# DLP.net
KiCad netlist of a schematic drawn in Altium Designer
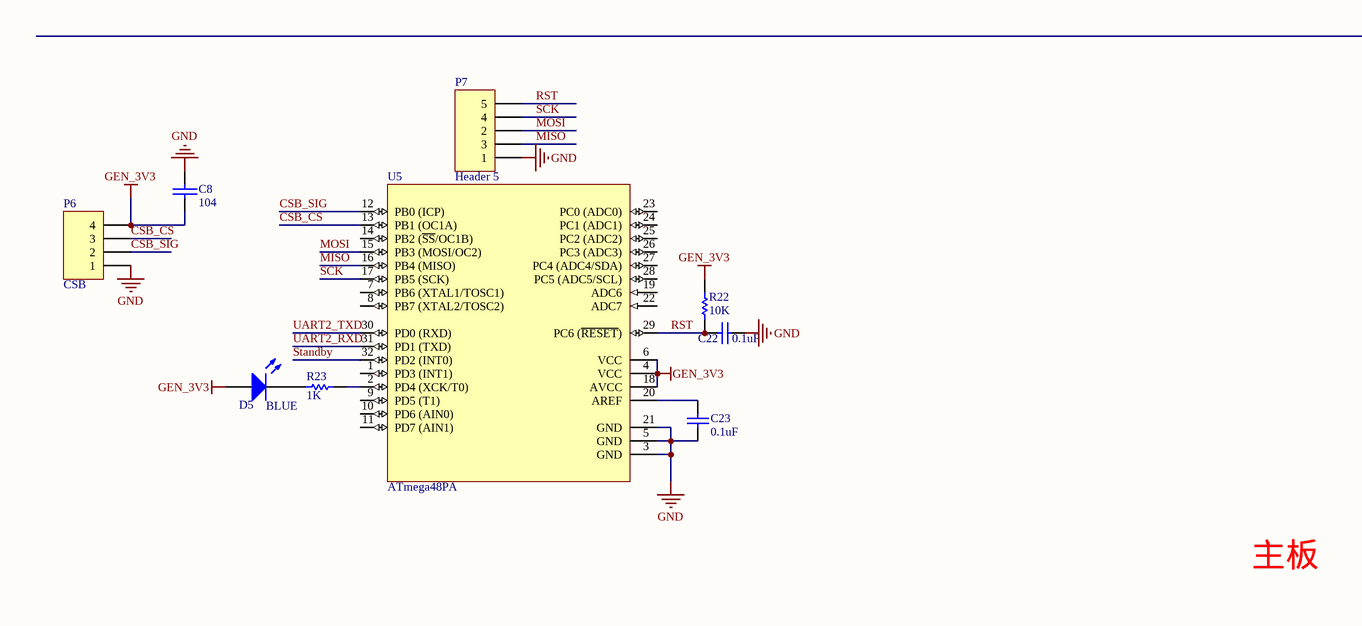
[diagram p0: DLP.SchDoc, top left]
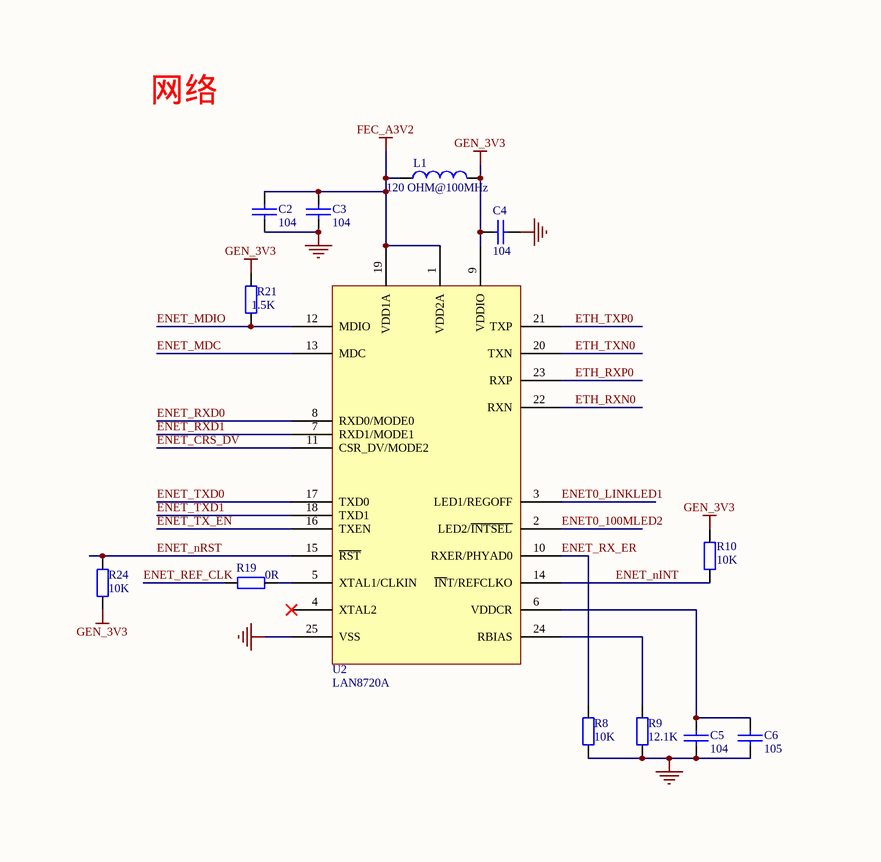
[diagram p1: DLP.SchDoc, top right]
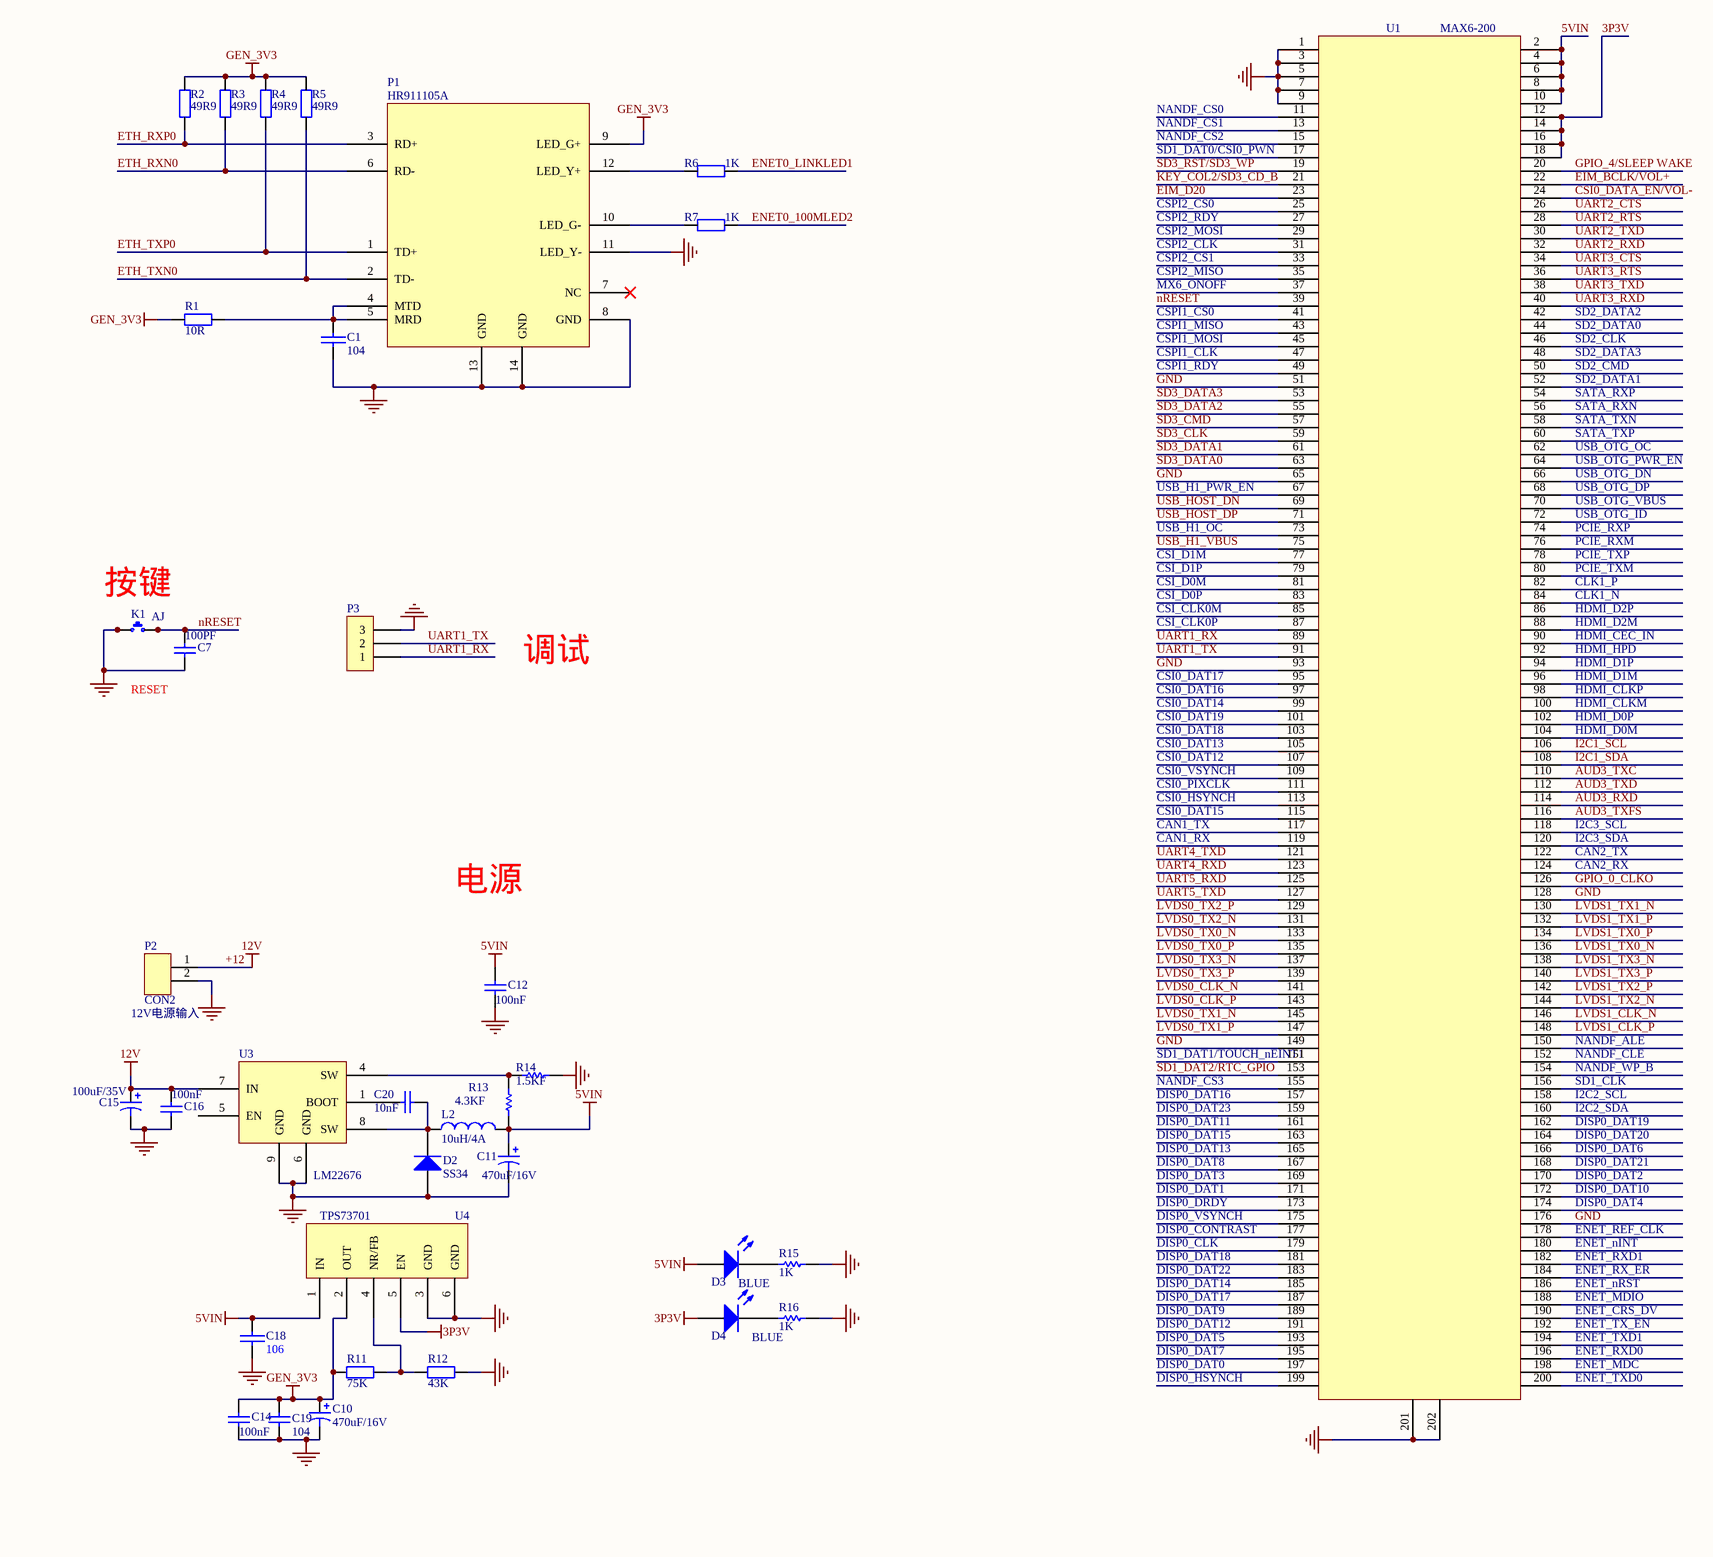
[diagram p2: DLP.SchDoc, bottom left]
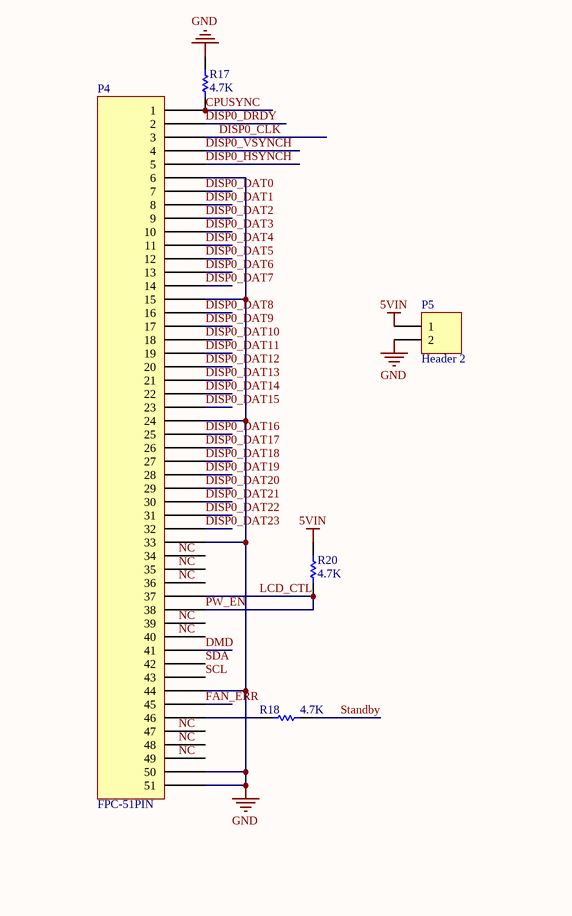
[diagram p3: DLP.SchDoc, bottom right]

(export (version "E")
  (design (tool "Eeschema 10.0.6"))
  (components
    (comp (ref "C1") (value "104") (footprint "0603") (libsource (lib "*") (part "CAP")))
    (comp (ref "C2") (value "104") (footprint "0603") (libsource (lib "*") (part "CAP")))
    (comp (ref "C3") (value "104") (footprint "0603") (libsource (lib "*") (part "CAP")))
    (comp (ref "C4") (value "104") (footprint "0603") (libsource (lib "*") (part "CAP")))
    (comp (ref "C5") (value "104") (footprint "0603") (libsource (lib "*") (part "CAP")))
    (comp (ref "C6") (value "105") (footprint "0603") (libsource (lib "*") (part "CAP")))
    (comp (ref "C7")
      (value "100PF")
      (footprint "0603")
      (description "Capacitor")
      (libsource (lib "*") (part "Cap"))
    )
    (comp (ref "C8") (value "104") (footprint "0603") (libsource (lib "*") (part "CAP")))
    (comp (ref "C10")
      (value "470uF/16V")
      (footprint "3216[1206]")
      (description "Polarized Capacitor (Radial)")
      (libsource (lib "*") (part "Cap Pol1"))
    )
    (comp (ref "C11")
      (value "470uF/16V")
      (footprint "C6.3*12")
      (description "Polarized Capacitor (Radial)")
      (libsource (lib "*") (part "Cap Pol1"))
    )
    (comp (ref "C12")
      (value "100nF")
      (footprint "0603")
      (description "Capacitor")
      (libsource (lib "*") (part "Cap"))
    )
    (comp (ref "C14")
      (value "100nF")
      (footprint "0603")
      (description "Capacitor")
      (libsource (lib "*") (part "Cap"))
    )
    (comp (ref "C15")
      (value "100uF/35V")
      (footprint "C6.3*12")
      (description "Polarized Capacitor (Radial)")
      (libsource (lib "*") (part "Cap Pol1"))
    )
    (comp (ref "C16")
      (value "100nF")
      (footprint "0603")
      (description "Capacitor")
      (libsource (lib "*") (part "Cap"))
    )
    (comp (ref "C18") (value "106") (footprint "0603") (libsource (lib "") (part "CAP_1")))
    (comp (ref "C19")
      (value "104")
      (footprint "0603")
      (fields (field (name "PUBLISHER") "Altium Limited"))
      (libsource (lib "*") (part "Cap"))
    )
    (comp (ref "C20")
      (value "10nF")
      (footprint "0603")
      (description "Capacitor")
      (libsource (lib "*") (part "Cap"))
    )
    (comp (ref "C22")
      (value "0.1uF")
      (footprint "0603")
      (description "Capacitor")
      (fields (field (name "Comment") "Cap") (field (name "PUBLISHER") "Altium Limited"))
      (libsource (lib "Miscellaneous Devices") (part "Cap"))
    )
    (comp (ref "C23")
      (value "0.1uF")
      (footprint "0603")
      (description "Capacitor")
      (fields (field (name "Comment") "Cap") (field (name "PUBLISHER") "Altium Limited"))
      (libsource (lib "Miscellaneous Devices") (part "Cap"))
    )
    (comp (ref "D2")
      (value "SS34")
      (footprint "SMA")
      (description "3 Amp Medium Power Silicon Rectifier Diode")
      (libsource (lib "*") (part "Diode 1N5408"))
    )
    (comp (ref "D3")
      (value "BLUE")
      (footprint "0603-LED")
      (description "Typical RED, GREEN, YELLOW, AMBER GaAs LED")
      (libsource (lib "*") (part "LED2"))
    )
    (comp (ref "D4")
      (value "BLUE")
      (footprint "0603-LED")
      (description "Typical RED, GREEN, YELLOW, AMBER GaAs LED")
      (libsource (lib "*") (part "LED2"))
    )
    (comp (ref "D5")
      (value "BLUE")
      (footprint "0603-LED")
      (description "Typical RED, GREEN, YELLOW, AMBER GaAs LED")
      (libsource (lib "*") (part "LED2"))
    )
    (comp (ref "K1") (value "AJ") (footprint "4*4*1.5") (libsource (lib "*") (part "KEY_1")))
    (comp (ref "L1")
      (value "120 OHM@100MHz")
      (footprint "0603")
      (description "Inductor")
      (libsource (lib "*") (part "Inductor"))
    )
    (comp (ref "L2")
      (value "10uH/4A")
      (footprint "8040")
      (description "Inductor")
      (libsource (lib "*") (part "Inductor"))
    )
    (comp (ref "P1") (value "HR911105A") (footprint "HR911105A") (libsource (lib "*") (part "HR911105A")))
    (comp (ref "P2") (value "CON2") (footprint "PH2.0-2P") (libsource (lib "*") (part "CON2")))
    (comp (ref "P3")
      (value "~")
      (footprint "HDR1X3")
      (description "Connector")
      (libsource (lib "*") (part "CON3"))
    )
    (comp (ref "P4")
      (value "FPC-51PIN")
      (footprint "FH26-51S-0.3SHW")
      (libsource (lib "TANK") (part "FPC-51PIN"))
    )
    (comp (ref "P5")
      (value "Header 2")
      (footprint "PH2.0-2P")
      (description "Header, 2-Pin")
      (fields (field (name "PUBLISHER") "Altium Limited"))
      (libsource (lib "Miscellaneous Connectors") (part "Header 2"))
    )
    (comp (ref "P6")
      (value "CSB")
      (footprint "HDR1X4")
      (description "Header, 4-Pin")
      (fields (field (name "PUBLISHER") "Altium Limited"))
      (libsource (lib "Miscellaneous Connectors") (part "Header 4"))
    )
    (comp (ref "P7")
      (value "Header 5")
      (footprint "HDR1X5")
      (description "Header, 5-Pin")
      (fields (field (name "PUBLISHER") "Altium Limited"))
      (libsource (lib "Miscellaneous Connectors") (part "Header 5"))
    )
    (comp (ref "R1") (value "10R") (footprint "0603") (libsource (lib "*") (part "RES")))
    (comp (ref "R2") (value "49R9") (footprint "0603") (libsource (lib "*") (part "RES")))
    (comp (ref "R3") (value "49R9") (footprint "0603") (libsource (lib "*") (part "RES")))
    (comp (ref "R4") (value "49R9") (footprint "0603") (libsource (lib "*") (part "RES")))
    (comp (ref "R5") (value "49R9") (footprint "0603") (libsource (lib "*") (part "RES")))
    (comp (ref "R6") (value "1K") (footprint "0603") (libsource (lib "*") (part "RES")))
    (comp (ref "R7") (value "1K") (footprint "0603") (libsource (lib "*") (part "RES")))
    (comp (ref "R8") (value "10K") (footprint "0603") (libsource (lib "*") (part "RES")))
    (comp (ref "R9") (value "12.1K") (footprint "0603") (libsource (lib "*") (part "RES")))
    (comp (ref "R10") (value "10K") (footprint "0603") (libsource (lib "*") (part "RES")))
    (comp (ref "R11")
      (value "75K")
      (footprint "0603")
      (description "Resistor")
      (fields (field (name "PUBLISHER") "Altium Limited"))
      (libsource (lib "*") (part "Res2"))
    )
    (comp (ref "R12")
      (value "43K")
      (footprint "0603")
      (description "Resistor")
      (fields (field (name "PUBLISHER") "Altium Limited"))
      (libsource (lib "") (part "Res2_1"))
    )
    (comp (ref "R13")
      (value "4.3KF")
      (footprint "0603")
      (description "Resistor")
      (libsource (lib "*") (part "Res1"))
    )
    (comp (ref "R14")
      (value "1.5KF")
      (footprint "0603")
      (description "Resistor")
      (libsource (lib "*") (part "Res1"))
    )
    (comp (ref "R15")
      (value "1K")
      (footprint "0603")
      (description "Resistor")
      (libsource (lib "*") (part "Res1"))
    )
    (comp (ref "R16")
      (value "1K")
      (footprint "0603")
      (description "Resistor")
      (libsource (lib "*") (part "Res1"))
    )
    (comp (ref "R17")
      (value "4.7K")
      (footprint "0603")
      (description "Resistor")
      (fields (field (name "Comment") "Res1") (field (name "PUBLISHER") "Altium Limited"))
      (libsource (lib "Miscellaneous Devices") (part "Res1"))
    )
    (comp (ref "R18")
      (value "4.7K")
      (footprint "0603")
      (description "Resistor")
      (fields (field (name "Comment") "Res1") (field (name "PUBLISHER") "Altium Limited"))
      (libsource (lib "Miscellaneous Devices") (part "Res1"))
    )
    (comp (ref "R19") (value "0R") (footprint "0603") (libsource (lib "*") (part "RES")))
    (comp (ref "R20")
      (value "4.7K")
      (footprint "0603")
      (description "Resistor")
      (fields (field (name "Comment") "Res1") (field (name "PUBLISHER") "Altium Limited"))
      (libsource (lib "Miscellaneous Devices") (part "Res1"))
    )
    (comp (ref "R21") (value "1.5K") (footprint "0603R") (libsource (lib "*") (part "RES")))
    (comp (ref "R22")
      (value "10K")
      (footprint "0603")
      (description "Resistor")
      (fields (field (name "Comment") "Res1") (field (name "PUBLISHER") "Altium Limited"))
      (libsource (lib "Miscellaneous Devices") (part "Res1"))
    )
    (comp (ref "R23")
      (value "1K")
      (footprint "0603")
      (description "Resistor")
      (libsource (lib "*") (part "Res1"))
    )
    (comp (ref "R24") (value "10K") (footprint "0603") (libsource (lib "*") (part "RES")))
    (comp (ref "U1") (value "MAX6-200") (footprint "SO-DIMM 200") (libsource (lib "*") (part "MAX6-200")))
    (comp (ref "U2") (value "LAN8720A") (footprint "QFN24_4X4MM") (libsource (lib "*") (part "LAN8720A")))
    (comp (ref "U3") (value "LM22676") (footprint "SO-8HP") (libsource (lib "*") (part "LM22676")))
    (comp (ref "U4") (value "TPS73701") (footprint "SOT223-6") (libsource (lib "*") (part "TPS737")))
    (comp (ref "U5")
      (value "ATmega48PA")
      (footprint "32A_M")
      (description "8-Bit AVR Microcontroller with 8K Bytes of In-System Programmable Flash Memory")
      (fields (field (name "PUBLISHER") "Altium Limited"))
      (libsource (lib "Atmel Microcontroller 8-Bit AVR") (part "ATmega8-16AC"))
    )
  )
  (nets
    (net (code "1") (name "/AUD3_RXD") (class "Default") (node (ref "U1") (pin "114") (pintype "passive")))
    (net (code "2") (name "/AUD3_TXC") (class "Default") (node (ref "U1") (pin "110") (pintype "passive")))
    (net (code "3") (name "/AUD3_TXD") (class "Default") (node (ref "U1") (pin "112") (pintype "passive")))
    (net (code "4") (name "/AUD3_TXFS") (class "Default") (node (ref "U1") (pin "116") (pintype "passive")))
    (net (code "5") (name "/CAN1_RX") (class "Default") (node (ref "U1") (pin "119") (pintype "passive")))
    (net (code "6") (name "/CAN1_TX") (class "Default") (node (ref "U1") (pin "117") (pintype "passive")))
    (net (code "7") (name "/CAN2_RX") (class "Default") (node (ref "U1") (pin "124") (pintype "passive")))
    (net (code "8") (name "/CAN2_TX") (class "Default") (node (ref "U1") (pin "122") (pintype "passive")))
    (net (code "9") (name "/CLK1_N") (class "Default") (node (ref "U1") (pin "84") (pintype "passive")))
    (net (code "10") (name "/CLK1_P") (class "Default") (node (ref "U1") (pin "82") (pintype "passive")))
    (net (code "11") (name "/CPUSYNC") (class "Default")
      (node (ref "P4") (pin "1") (pinfunction "1_1") (pintype "passive"))
      (node (ref "R17") (pin "2") (pinfunction "2_2") (pintype "passive"))
    )
    (net (code "12") (name "/CSB_CS") (class "Default")
      (node (ref "P6") (pin "3") (pinfunction "3_3") (pintype "passive"))
      (node (ref "U5") (pin "13") (pinfunction "PB1_(OC1A)_13") (pintype "bidirectional"))
    )
    (net (code "13") (name "/CSB_SIG") (class "Default")
      (node (ref "P6") (pin "2") (pinfunction "2_2") (pintype "passive"))
      (node (ref "U5") (pin "12") (pinfunction "PB0_(ICP)_12") (pintype "bidirectional"))
    )
    (net (code "14") (name "/CSI0_DAT12") (class "Default") (node (ref "U1") (pin "107") (pintype "passive")))
    (net (code "15") (name "/CSI0_DAT13") (class "Default") (node (ref "U1") (pin "105") (pintype "passive")))
    (net (code "16") (name "/CSI0_DAT14") (class "Default") (node (ref "U1") (pin "99") (pintype "passive")))
    (net (code "17") (name "/CSI0_DAT15") (class "Default") (node (ref "U1") (pin "115") (pintype "passive")))
    (net (code "18") (name "/CSI0_DAT16") (class "Default") (node (ref "U1") (pin "97") (pintype "passive")))
    (net (code "19") (name "/CSI0_DAT17") (class "Default") (node (ref "U1") (pin "95") (pintype "passive")))
    (net (code "20") (name "/CSI0_DAT18") (class "Default") (node (ref "U1") (pin "103") (pintype "passive")))
    (net (code "21") (name "/CSI0_DAT19") (class "Default") (node (ref "U1") (pin "101") (pintype "passive")))
    (net (code "22") (name "/CSI0_DATA_EN{slash}VOL-") (class "Default")
      (node (ref "U1") (pin "24") (pintype "passive"))
    )
    (net (code "23") (name "/CSI0_HSYNCH") (class "Default")
      (node (ref "U1") (pin "113") (pintype "passive"))
    )
    (net (code "24") (name "/CSI0_PIXCLK") (class "Default")
      (node (ref "U1") (pin "111") (pintype "passive"))
    )
    (net (code "25") (name "/CSI0_VSYNCH") (class "Default")
      (node (ref "U1") (pin "109") (pintype "passive"))
    )
    (net (code "26") (name "/CSI_CLK0M") (class "Default") (node (ref "U1") (pin "85") (pintype "passive")))
    (net (code "27") (name "/CSI_CLK0P") (class "Default") (node (ref "U1") (pin "87") (pintype "passive")))
    (net (code "28") (name "/CSI_D0M") (class "Default") (node (ref "U1") (pin "81") (pintype "passive")))
    (net (code "29") (name "/CSI_D0P") (class "Default") (node (ref "U1") (pin "83") (pintype "passive")))
    (net (code "30") (name "/CSI_D1M") (class "Default") (node (ref "U1") (pin "77") (pintype "passive")))
    (net (code "31") (name "/CSI_D1P") (class "Default") (node (ref "U1") (pin "79") (pintype "passive")))
    (net (code "32") (name "/CSPI1_CLK") (class "Default") (node (ref "U1") (pin "47") (pintype "passive")))
    (net (code "33") (name "/CSPI1_CS0") (class "Default") (node (ref "U1") (pin "41") (pintype "passive")))
    (net (code "34") (name "/CSPI1_MISO") (class "Default") (node (ref "U1") (pin "43") (pintype "passive")))
    (net (code "35") (name "/CSPI1_MOSI") (class "Default") (node (ref "U1") (pin "45") (pintype "passive")))
    (net (code "36") (name "/CSPI1_RDY") (class "Default") (node (ref "U1") (pin "49") (pintype "passive")))
    (net (code "37") (name "/CSPI2_CLK") (class "Default") (node (ref "U1") (pin "31") (pintype "passive")))
    (net (code "38") (name "/CSPI2_CS0") (class "Default") (node (ref "U1") (pin "25") (pintype "passive")))
    (net (code "39") (name "/CSPI2_CS1") (class "Default") (node (ref "U1") (pin "33") (pintype "passive")))
    (net (code "40") (name "/CSPI2_MISO") (class "Default") (node (ref "U1") (pin "35") (pintype "passive")))
    (net (code "41") (name "/CSPI2_MOSI") (class "Default") (node (ref "U1") (pin "29") (pintype "passive")))
    (net (code "42") (name "/CSPI2_RDY") (class "Default") (node (ref "U1") (pin "27") (pintype "passive")))
    (net (code "43") (name "/DISP0_CLK") (class "Default")
      (node (ref "P4") (pin "3") (pinfunction "3_3") (pintype "passive"))
      (node (ref "U1") (pin "179") (pintype "passive"))
    )
    (net (code "44") (name "/DISP0_CONTRAST") (class "Default")
      (node (ref "U1") (pin "177") (pintype "passive"))
    )
    (net (code "45") (name "/DISP0_DAT0") (class "Default")
      (node (ref "P4") (pin "7") (pinfunction "7_7") (pintype "passive"))
      (node (ref "U1") (pin "197") (pintype "passive"))
    )
    (net (code "46") (name "/DISP0_DAT1") (class "Default")
      (node (ref "P4") (pin "8") (pinfunction "8_8") (pintype "passive"))
      (node (ref "U1") (pin "171") (pintype "passive"))
    )
    (net (code "47") (name "/DISP0_DAT2") (class "Default")
      (node (ref "P4") (pin "9") (pinfunction "9_9") (pintype "passive"))
      (node (ref "U1") (pin "170") (pintype "passive"))
    )
    (net (code "48") (name "/DISP0_DAT3") (class "Default")
      (node (ref "P4") (pin "10") (pinfunction "10_10") (pintype "passive"))
      (node (ref "U1") (pin "169") (pintype "passive"))
    )
    (net (code "49") (name "/DISP0_DAT4") (class "Default")
      (node (ref "P4") (pin "11") (pinfunction "11_11") (pintype "passive"))
      (node (ref "U1") (pin "174") (pintype "passive"))
    )
    (net (code "50") (name "/DISP0_DAT5") (class "Default")
      (node (ref "P4") (pin "12") (pinfunction "12_12") (pintype "passive"))
      (node (ref "U1") (pin "193") (pintype "passive"))
    )
    (net (code "51") (name "/DISP0_DAT6") (class "Default")
      (node (ref "P4") (pin "13") (pinfunction "13_13") (pintype "passive"))
      (node (ref "U1") (pin "166") (pintype "passive"))
    )
    (net (code "52") (name "/DISP0_DAT7") (class "Default")
      (node (ref "P4") (pin "14") (pinfunction "14_14") (pintype "passive"))
      (node (ref "U1") (pin "195") (pintype "passive"))
    )
    (net (code "53") (name "/DISP0_DAT8") (class "Default")
      (node (ref "P4") (pin "16") (pinfunction "16_16") (pintype "passive"))
      (node (ref "U1") (pin "167") (pintype "passive"))
    )
    (net (code "54") (name "/DISP0_DAT9") (class "Default")
      (node (ref "P4") (pin "17") (pinfunction "17_17") (pintype "passive"))
      (node (ref "U1") (pin "189") (pintype "passive"))
    )
    (net (code "55") (name "/DISP0_DAT10") (class "Default")
      (node (ref "P4") (pin "18") (pinfunction "18_18") (pintype "passive"))
      (node (ref "U1") (pin "172") (pintype "passive"))
    )
    (net (code "56") (name "/DISP0_DAT11") (class "Default")
      (node (ref "P4") (pin "19") (pinfunction "19_19") (pintype "passive"))
      (node (ref "U1") (pin "161") (pintype "passive"))
    )
    (net (code "57") (name "/DISP0_DAT12") (class "Default")
      (node (ref "P4") (pin "20") (pinfunction "20_20") (pintype "passive"))
      (node (ref "U1") (pin "191") (pintype "passive"))
    )
    (net (code "58") (name "/DISP0_DAT13") (class "Default")
      (node (ref "P4") (pin "21") (pinfunction "21_21") (pintype "passive"))
      (node (ref "U1") (pin "165") (pintype "passive"))
    )
    (net (code "59") (name "/DISP0_DAT14") (class "Default")
      (node (ref "P4") (pin "22") (pinfunction "22_22") (pintype "passive"))
      (node (ref "U1") (pin "185") (pintype "passive"))
    )
    (net (code "60") (name "/DISP0_DAT15") (class "Default")
      (node (ref "P4") (pin "23") (pinfunction "23_23") (pintype "passive"))
      (node (ref "U1") (pin "163") (pintype "passive"))
    )
    (net (code "61") (name "/DISP0_DAT16") (class "Default")
      (node (ref "P4") (pin "25") (pinfunction "25_25") (pintype "passive"))
      (node (ref "U1") (pin "157") (pintype "passive"))
    )
    (net (code "62") (name "/DISP0_DAT17") (class "Default")
      (node (ref "P4") (pin "26") (pinfunction "26_26") (pintype "passive"))
      (node (ref "U1") (pin "187") (pintype "passive"))
    )
    (net (code "63") (name "/DISP0_DAT18") (class "Default")
      (node (ref "P4") (pin "27") (pinfunction "27_27") (pintype "passive"))
      (node (ref "U1") (pin "181") (pintype "passive"))
    )
    (net (code "64") (name "/DISP0_DAT19") (class "Default")
      (node (ref "P4") (pin "28") (pinfunction "28_28") (pintype "passive"))
      (node (ref "U1") (pin "162") (pintype "passive"))
    )
    (net (code "65") (name "/DISP0_DAT20") (class "Default")
      (node (ref "P4") (pin "29") (pinfunction "29_29") (pintype "passive"))
      (node (ref "U1") (pin "164") (pintype "passive"))
    )
    (net (code "66") (name "/DISP0_DAT21") (class "Default")
      (node (ref "P4") (pin "30") (pinfunction "30_30") (pintype "passive"))
      (node (ref "U1") (pin "168") (pintype "passive"))
    )
    (net (code "67") (name "/DISP0_DAT22") (class "Default")
      (node (ref "P4") (pin "31") (pinfunction "31_31") (pintype "passive"))
      (node (ref "U1") (pin "183") (pintype "passive"))
    )
    (net (code "68") (name "/DISP0_DAT23") (class "Default")
      (node (ref "P4") (pin "32") (pinfunction "32_32") (pintype "passive"))
      (node (ref "U1") (pin "159") (pintype "passive"))
    )
    (net (code "69") (name "/DISP0_DRDY") (class "Default")
      (node (ref "P4") (pin "2") (pinfunction "2_2") (pintype "passive"))
      (node (ref "U1") (pin "173") (pintype "passive"))
    )
    (net (code "70") (name "/DISP0_HSYNCH") (class "Default")
      (node (ref "P4") (pin "5") (pinfunction "5_5") (pintype "passive"))
      (node (ref "U1") (pin "199") (pintype "passive"))
    )
    (net (code "71") (name "/DISP0_VSYNCH") (class "Default")
      (node (ref "P4") (pin "4") (pinfunction "4_4") (pintype "passive"))
      (node (ref "U1") (pin "175") (pintype "passive"))
    )
    (net (code "72") (name "/DMD") (class "Default")
      (node (ref "P4") (pin "41") (pinfunction "41_41") (pintype "passive"))
    )
    (net (code "73") (name "/EIM_BCLK{slash}VOL+") (class "Default")
      (node (ref "U1") (pin "22") (pintype "passive"))
    )
    (net (code "74") (name "/EIM_D20") (class "Default") (node (ref "U1") (pin "23") (pintype "passive")))
    (net (code "75") (name "/ENET0_100MLED2") (class "Default")
      (node (ref "R7") (pin "2") (pinfunction "2_2") (pintype "passive"))
      (node (ref "U2") (pin "2") (pinfunction "LED2/~{INTSEL}_2") (pintype "passive"))
    )
    (net (code "76") (name "/ENET0_LINKLED1") (class "Default")
      (node (ref "R6") (pin "2") (pinfunction "2_2") (pintype "passive"))
      (node (ref "U2") (pin "3") (pinfunction "LED1/REGOFF_3") (pintype "passive"))
    )
    (net (code "77") (name "/ENET_CRS_DV") (class "Default")
      (node (ref "U1") (pin "190") (pintype "passive"))
      (node (ref "U2") (pin "11") (pinfunction "CSR_DV/MODE2_11") (pintype "passive"))
    )
    (net (code "78") (name "/ENET_MDC") (class "Default")
      (node (ref "U1") (pin "198") (pintype "passive"))
      (node (ref "U2") (pin "13") (pinfunction "MDC_13") (pintype "passive"))
    )
    (net (code "79") (name "/ENET_MDIO") (class "Default")
      (node (ref "R21") (pin "1") (pinfunction "1_1") (pintype "passive"))
      (node (ref "U1") (pin "188") (pintype "passive"))
      (node (ref "U2") (pin "12") (pinfunction "MDIO_12") (pintype "passive"))
    )
    (net (code "80") (name "/ENET_REF_CLK") (class "Default")
      (node (ref "R19") (pin "2") (pinfunction "2_2") (pintype "passive"))
      (node (ref "U1") (pin "178") (pintype "passive"))
    )
    (net (code "81") (name "/ENET_RXD0") (class "Default")
      (node (ref "U1") (pin "196") (pintype "passive"))
      (node (ref "U2") (pin "8") (pinfunction "RXD0/MODE0_8") (pintype "passive"))
    )
    (net (code "82") (name "/ENET_RXD1") (class "Default")
      (node (ref "U1") (pin "182") (pintype "passive"))
      (node (ref "U2") (pin "7") (pinfunction "RXD1/MODE1_7") (pintype "passive"))
    )
    (net (code "83") (name "/ENET_RX_ER") (class "Default")
      (node (ref "R8") (pin "2") (pinfunction "2_2") (pintype "passive"))
      (node (ref "U1") (pin "184") (pintype "passive"))
      (node (ref "U2") (pin "10") (pinfunction "RXER/PHYAD0_10") (pintype "passive"))
    )
    (net (code "84") (name "/ENET_TXD0") (class "Default")
      (node (ref "U1") (pin "200") (pintype "passive"))
      (node (ref "U2") (pin "17") (pinfunction "TXD0_17") (pintype "passive"))
    )
    (net (code "85") (name "/ENET_TXD1") (class "Default")
      (node (ref "U1") (pin "194") (pintype "passive"))
      (node (ref "U2") (pin "18") (pinfunction "TXD1_18") (pintype "passive"))
    )
    (net (code "86") (name "/ENET_TX_EN") (class "Default")
      (node (ref "U1") (pin "192") (pintype "passive"))
      (node (ref "U2") (pin "16") (pinfunction "TXEN_16") (pintype "passive"))
    )
    (net (code "87") (name "/ENET_nINT") (class "Default")
      (node (ref "R10") (pin "1") (pinfunction "1_1") (pintype "passive"))
      (node (ref "U1") (pin "180") (pintype "passive"))
      (node (ref "U2") (pin "14") (pinfunction "~{IN}T/REFCLKO_14") (pintype "passive"))
    )
    (net (code "88") (name "/ENET_nRST") (class "Default")
      (node (ref "R24") (pin "2") (pinfunction "2_2") (pintype "passive"))
      (node (ref "U1") (pin "186") (pintype "passive"))
      (node (ref "U2") (pin "15") (pinfunction "~{RST}_15") (pintype "passive"))
    )
    (net (code "89") (name "/ETH_RXN0") (class "Default")
      (node (ref "P1") (pin "6") (pinfunction "RD-_6") (pintype "passive"))
      (node (ref "R3") (pin "1") (pinfunction "1_1") (pintype "passive"))
      (node (ref "U2") (pin "22") (pinfunction "RXN_22") (pintype "passive"))
    )
    (net (code "90") (name "/ETH_RXP0") (class "Default")
      (node (ref "P1") (pin "3") (pinfunction "RD+_3") (pintype "passive"))
      (node (ref "R2") (pin "1") (pinfunction "1_1") (pintype "passive"))
      (node (ref "U2") (pin "23") (pinfunction "RXP_23") (pintype "passive"))
    )
    (net (code "91") (name "/ETH_TXN0") (class "Default")
      (node (ref "P1") (pin "2") (pinfunction "TD-_2") (pintype "passive"))
      (node (ref "R5") (pin "1") (pinfunction "1_1") (pintype "passive"))
      (node (ref "U2") (pin "20") (pinfunction "TXN_20") (pintype "passive"))
    )
    (net (code "92") (name "/ETH_TXP0") (class "Default")
      (node (ref "P1") (pin "1") (pinfunction "TD+_1") (pintype "passive"))
      (node (ref "R4") (pin "1") (pinfunction "1_1") (pintype "passive"))
      (node (ref "U2") (pin "21") (pinfunction "TXP_21") (pintype "passive"))
    )
    (net (code "93") (name "/FAN_ERR") (class "Default")
      (node (ref "P4") (pin "45") (pinfunction "45_45") (pintype "passive"))
    )
    (net (code "94") (name "/GPIO_0_CLKO") (class "Default")
      (node (ref "U1") (pin "126") (pintype "passive"))
    )
    (net (code "95") (name "/GPIO_4{slash}SLEEP WAKE") (class "Default")
      (node (ref "U1") (pin "20") (pintype "passive"))
    )
    (net (code "96") (name "/HDMI_CEC_IN") (class "Default") (node (ref "U1") (pin "90") (pintype "passive")))
    (net (code "97") (name "/HDMI_CLKM") (class "Default") (node (ref "U1") (pin "100") (pintype "passive")))
    (net (code "98") (name "/HDMI_CLKP") (class "Default") (node (ref "U1") (pin "98") (pintype "passive")))
    (net (code "99") (name "/HDMI_D0M") (class "Default") (node (ref "U1") (pin "104") (pintype "passive")))
    (net (code "100") (name "/HDMI_D0P") (class "Default") (node (ref "U1") (pin "102") (pintype "passive")))
    (net (code "101") (name "/HDMI_D1M") (class "Default") (node (ref "U1") (pin "96") (pintype "passive")))
    (net (code "102") (name "/HDMI_D1P") (class "Default") (node (ref "U1") (pin "94") (pintype "passive")))
    (net (code "103") (name "/HDMI_D2M") (class "Default") (node (ref "U1") (pin "88") (pintype "passive")))
    (net (code "104") (name "/HDMI_D2P") (class "Default") (node (ref "U1") (pin "86") (pintype "passive")))
    (net (code "105") (name "/HDMI_HPD") (class "Default") (node (ref "U1") (pin "92") (pintype "passive")))
    (net (code "106") (name "/I2C1_SCL") (class "Default") (node (ref "U1") (pin "106") (pintype "passive")))
    (net (code "107") (name "/I2C1_SDA") (class "Default") (node (ref "U1") (pin "108") (pintype "passive")))
    (net (code "108") (name "/I2C2_SCL") (class "Default") (node (ref "U1") (pin "158") (pintype "passive")))
    (net (code "109") (name "/I2C2_SDA") (class "Default") (node (ref "U1") (pin "160") (pintype "passive")))
    (net (code "110") (name "/I2C3_SCL") (class "Default") (node (ref "U1") (pin "118") (pintype "passive")))
    (net (code "111") (name "/I2C3_SDA") (class "Default") (node (ref "U1") (pin "120") (pintype "passive")))
    (net (code "112") (name "/KEY_COL2{slash}SD3_CD_B") (class "Default")
      (node (ref "U1") (pin "21") (pintype "passive"))
    )
    (net (code "113") (name "/LCD_CTL") (class "Default")
      (node (ref "P4") (pin "37") (pinfunction "37_37") (pintype "passive"))
      (node (ref "P4") (pin "38") (pinfunction "38_38") (pintype "passive"))
      (node (ref "R20") (pin "2") (pinfunction "2_2") (pintype "passive"))
    )
    (net (code "114") (name "/LVDS0_CLK_N") (class "Default")
      (node (ref "U1") (pin "141") (pintype "passive"))
    )
    (net (code "115") (name "/LVDS0_CLK_P") (class "Default")
      (node (ref "U1") (pin "143") (pintype "passive"))
    )
    (net (code "116") (name "/LVDS0_TX0_N") (class "Default")
      (node (ref "U1") (pin "133") (pintype "passive"))
    )
    (net (code "117") (name "/LVDS0_TX0_P") (class "Default")
      (node (ref "U1") (pin "135") (pintype "passive"))
    )
    (net (code "118") (name "/LVDS0_TX1_N") (class "Default")
      (node (ref "U1") (pin "145") (pintype "passive"))
    )
    (net (code "119") (name "/LVDS0_TX1_P") (class "Default")
      (node (ref "U1") (pin "147") (pintype "passive"))
    )
    (net (code "120") (name "/LVDS0_TX2_N") (class "Default")
      (node (ref "U1") (pin "131") (pintype "passive"))
    )
    (net (code "121") (name "/LVDS0_TX2_P") (class "Default")
      (node (ref "U1") (pin "129") (pintype "passive"))
    )
    (net (code "122") (name "/LVDS0_TX3_N") (class "Default")
      (node (ref "U1") (pin "137") (pintype "passive"))
    )
    (net (code "123") (name "/LVDS0_TX3_P") (class "Default")
      (node (ref "U1") (pin "139") (pintype "passive"))
    )
    (net (code "124") (name "/LVDS1_CLK_N") (class "Default")
      (node (ref "U1") (pin "146") (pintype "passive"))
    )
    (net (code "125") (name "/LVDS1_CLK_P") (class "Default")
      (node (ref "U1") (pin "148") (pintype "passive"))
    )
    (net (code "126") (name "/LVDS1_TX0_N") (class "Default")
      (node (ref "U1") (pin "136") (pintype "passive"))
    )
    (net (code "127") (name "/LVDS1_TX0_P") (class "Default")
      (node (ref "U1") (pin "134") (pintype "passive"))
    )
    (net (code "128") (name "/LVDS1_TX1_N") (class "Default")
      (node (ref "U1") (pin "130") (pintype "passive"))
    )
    (net (code "129") (name "/LVDS1_TX1_P") (class "Default")
      (node (ref "U1") (pin "132") (pintype "passive"))
    )
    (net (code "130") (name "/LVDS1_TX2_N") (class "Default")
      (node (ref "U1") (pin "144") (pintype "passive"))
    )
    (net (code "131") (name "/LVDS1_TX2_P") (class "Default")
      (node (ref "U1") (pin "142") (pintype "passive"))
    )
    (net (code "132") (name "/LVDS1_TX3_N") (class "Default")
      (node (ref "U1") (pin "138") (pintype "passive"))
    )
    (net (code "133") (name "/LVDS1_TX3_P") (class "Default")
      (node (ref "U1") (pin "140") (pintype "passive"))
    )
    (net (code "134") (name "/MISO") (class "Default")
      (node (ref "P7") (pin "3") (pinfunction "3_3") (pintype "passive"))
      (node (ref "U5") (pin "16") (pinfunction "PB4_(MISO)_16") (pintype "bidirectional"))
    )
    (net (code "135") (name "/MOSI") (class "Default")
      (node (ref "P7") (pin "2") (pinfunction "2_2") (pintype "passive"))
      (node (ref "U5") (pin "15") (pinfunction "PB3_(MOSI/OC2)_15") (pintype "bidirectional"))
    )
    (net (code "136") (name "/MX6_ONOFF") (class "Default") (node (ref "U1") (pin "37") (pintype "passive")))
    (net (code "137") (name "/NANDF_ALE") (class "Default") (node (ref "U1") (pin "150") (pintype "passive")))
    (net (code "138") (name "/NANDF_CLE") (class "Default") (node (ref "U1") (pin "152") (pintype "passive")))
    (net (code "139") (name "/NANDF_CS0") (class "Default") (node (ref "U1") (pin "11") (pintype "passive")))
    (net (code "140") (name "/NANDF_CS1") (class "Default") (node (ref "U1") (pin "13") (pintype "passive")))
    (net (code "141") (name "/NANDF_CS2") (class "Default") (node (ref "U1") (pin "15") (pintype "passive")))
    (net (code "142") (name "/NANDF_CS3") (class "Default") (node (ref "U1") (pin "155") (pintype "passive")))
    (net (code "143") (name "/NANDF_WP_B") (class "Default")
      (node (ref "U1") (pin "154") (pintype "passive"))
    )
    (net (code "145") (name "/PCIE_RXM") (class "Default") (node (ref "U1") (pin "76") (pintype "passive")))
    (net (code "146") (name "/PCIE_RXP") (class "Default") (node (ref "U1") (pin "74") (pintype "passive")))
    (net (code "147") (name "/PCIE_TXM") (class "Default") (node (ref "U1") (pin "80") (pintype "passive")))
    (net (code "148") (name "/PCIE_TXP") (class "Default") (node (ref "U1") (pin "78") (pintype "passive")))
    (net (code "149") (name "/RST") (class "Default")
      (node (ref "C22") (pin "1") (pinfunction "1_1") (pintype "passive"))
      (node (ref "P7") (pin "5") (pinfunction "5_5") (pintype "passive"))
      (node (ref "R22") (pin "1") (pinfunction "1_1") (pintype "passive"))
      (node (ref "U5") (pin "29") (pinfunction "PC6_(~{RESET})_29") (pintype "bidirectional"))
    )
    (net (code "150") (name "/SATA_RXN") (class "Default") (node (ref "U1") (pin "56") (pintype "passive")))
    (net (code "151") (name "/SATA_RXP") (class "Default") (node (ref "U1") (pin "54") (pintype "passive")))
    (net (code "152") (name "/SATA_TXN") (class "Default") (node (ref "U1") (pin "58") (pintype "passive")))
    (net (code "153") (name "/SATA_TXP") (class "Default") (node (ref "U1") (pin "60") (pintype "passive")))
    (net (code "154") (name "/SCK") (class "Default")
      (node (ref "P7") (pin "4") (pinfunction "4_4") (pintype "passive"))
      (node (ref "U5") (pin "17") (pinfunction "PB5_(SCK)_17") (pintype "bidirectional"))
    )
    (net (code "155") (name "/SCL") (class "Default")
      (node (ref "P4") (pin "43") (pinfunction "43_43") (pintype "passive"))
    )
    (net (code "156") (name "/SD1_CLK") (class "Default") (node (ref "U1") (pin "156") (pintype "passive")))
    (net (code "157") (name "/SD1_DAT0{slash}CSI0_PWN") (class "Default")
      (node (ref "U1") (pin "17") (pintype "passive"))
    )
    (net (code "158") (name "/SD1_DAT1{slash}TOUCH_nEINT1") (class "Default")
      (node (ref "U1") (pin "151") (pintype "passive"))
    )
    (net (code "159") (name "/SD1_DAT2{slash}RTC_GPIO") (class "Default")
      (node (ref "U1") (pin "153") (pintype "passive"))
    )
    (net (code "160") (name "/SD2_CLK") (class "Default") (node (ref "U1") (pin "46") (pintype "passive")))
    (net (code "161") (name "/SD2_CMD") (class "Default") (node (ref "U1") (pin "50") (pintype "passive")))
    (net (code "162") (name "/SD2_DATA0") (class "Default") (node (ref "U1") (pin "44") (pintype "passive")))
    (net (code "163") (name "/SD2_DATA1") (class "Default") (node (ref "U1") (pin "52") (pintype "passive")))
    (net (code "164") (name "/SD2_DATA2") (class "Default") (node (ref "U1") (pin "42") (pintype "passive")))
    (net (code "165") (name "/SD2_DATA3") (class "Default") (node (ref "U1") (pin "48") (pintype "passive")))
    (net (code "166") (name "/SD3_CLK") (class "Default") (node (ref "U1") (pin "59") (pintype "passive")))
    (net (code "167") (name "/SD3_CMD") (class "Default") (node (ref "U1") (pin "57") (pintype "passive")))
    (net (code "168") (name "/SD3_DATA0") (class "Default") (node (ref "U1") (pin "63") (pintype "passive")))
    (net (code "169") (name "/SD3_DATA1") (class "Default") (node (ref "U1") (pin "61") (pintype "passive")))
    (net (code "170") (name "/SD3_DATA2") (class "Default") (node (ref "U1") (pin "55") (pintype "passive")))
    (net (code "171") (name "/SD3_DATA3") (class "Default") (node (ref "U1") (pin "53") (pintype "passive")))
    (net (code "172") (name "/SD3_RST{slash}SD3_WP") (class "Default")
      (node (ref "U1") (pin "19") (pintype "passive"))
    )
    (net (code "173") (name "/SDA") (class "Default")
      (node (ref "P4") (pin "42") (pinfunction "42_42") (pintype "passive"))
    )
    (net (code "174") (name "/Standby") (class "Default")
      (node (ref "R18") (pin "2") (pinfunction "2_2") (pintype "passive"))
      (node (ref "U5") (pin "32") (pinfunction "PD2_(INT0)_32") (pintype "bidirectional"))
    )
    (net (code "175") (name "/UART1_RX") (class "Default")
      (node (ref "P3") (pin "1") (pinfunction "1_1") (pintype "passive"))
      (node (ref "U1") (pin "89") (pintype "passive"))
    )
    (net (code "176") (name "/UART1_TX") (class "Default")
      (node (ref "P3") (pin "2") (pinfunction "2_2") (pintype "passive"))
      (node (ref "U1") (pin "91") (pintype "passive"))
    )
    (net (code "177") (name "/UART2_CTS") (class "Default") (node (ref "U1") (pin "26") (pintype "passive")))
    (net (code "178") (name "/UART2_RTS") (class "Default") (node (ref "U1") (pin "28") (pintype "passive")))
    (net (code "179") (name "/UART2_RXD") (class "Default")
      (node (ref "U1") (pin "32") (pintype "passive"))
      (node (ref "U5") (pin "31") (pinfunction "PD1_(TXD)_31") (pintype "bidirectional"))
    )
    (net (code "180") (name "/UART2_TXD") (class "Default")
      (node (ref "U1") (pin "30") (pintype "passive"))
      (node (ref "U5") (pin "30") (pinfunction "PD0_(RXD)_30") (pintype "bidirectional"))
    )
    (net (code "181") (name "/UART3_CTS") (class "Default") (node (ref "U1") (pin "34") (pintype "passive")))
    (net (code "182") (name "/UART3_RTS") (class "Default") (node (ref "U1") (pin "36") (pintype "passive")))
    (net (code "183") (name "/UART3_RXD") (class "Default") (node (ref "U1") (pin "40") (pintype "passive")))
    (net (code "184") (name "/UART3_TXD") (class "Default") (node (ref "U1") (pin "38") (pintype "passive")))
    (net (code "185") (name "/UART4_RXD") (class "Default") (node (ref "U1") (pin "123") (pintype "passive")))
    (net (code "186") (name "/UART4_TXD") (class "Default") (node (ref "U1") (pin "121") (pintype "passive")))
    (net (code "187") (name "/UART5_RXD") (class "Default") (node (ref "U1") (pin "125") (pintype "passive")))
    (net (code "188") (name "/UART5_TXD") (class "Default") (node (ref "U1") (pin "127") (pintype "passive")))
    (net (code "189") (name "/USB_H1_OC") (class "Default") (node (ref "U1") (pin "73") (pintype "passive")))
    (net (code "190") (name "/USB_H1_PWR_EN") (class "Default")
      (node (ref "U1") (pin "67") (pintype "passive"))
    )
    (net (code "191") (name "/USB_H1_VBUS") (class "Default")
      (node (ref "U1") (pin "75") (pintype "passive"))
    )
    (net (code "192") (name "/USB_HOST_DN") (class "Default")
      (node (ref "U1") (pin "69") (pintype "passive"))
    )
    (net (code "193") (name "/USB_HOST_DP") (class "Default")
      (node (ref "U1") (pin "71") (pintype "passive"))
    )
    (net (code "194") (name "/USB_OTG_DN") (class "Default") (node (ref "U1") (pin "66") (pintype "passive")))
    (net (code "195") (name "/USB_OTG_DP") (class "Default") (node (ref "U1") (pin "68") (pintype "passive")))
    (net (code "196") (name "/USB_OTG_ID") (class "Default") (node (ref "U1") (pin "72") (pintype "passive")))
    (net (code "197") (name "/USB_OTG_OC") (class "Default") (node (ref "U1") (pin "62") (pintype "passive")))
    (net (code "198") (name "/USB_OTG_PWR_EN") (class "Default")
      (node (ref "U1") (pin "64") (pintype "passive"))
    )
    (net (code "199") (name "/USB_OTG_VBUS") (class "Default")
      (node (ref "U1") (pin "70") (pintype "passive"))
    )
    (net (code "200") (name "/nRESET") (class "Default")
      (node (ref "C7") (pin "2") (pinfunction "2_2") (pintype "passive"))
      (node (ref "K1") (pin "3") (pintype "passive"))
      (node (ref "K1") (pin "4") (pintype "passive"))
      (node (ref "U1") (pin "39") (pintype "passive"))
    )
    (net (code "201") (name "3P3V") (class "Default")
      (node (ref "D4") (pin "1") (pinfunction "A_1") (pintype "passive"))
      (node (ref "U1") (pin "12") (pintype "passive"))
      (node (ref "U1") (pin "14") (pintype "passive"))
      (node (ref "U1") (pin "16") (pintype "passive"))
      (node (ref "U1") (pin "18") (pintype "passive"))
      (node (ref "U4") (pin "5") (pinfunction "EN_5") (pintype "passive"))
    )
    (net (code "202") (name "5VIN") (class "Default")
      (node (ref "C11") (pin "1") (pinfunction "1_1") (pintype "passive"))
      (node (ref "C12") (pin "2") (pinfunction "2_2") (pintype "passive"))
      (node (ref "C18") (pin "1") (pintype "passive"))
      (node (ref "D3") (pin "1") (pinfunction "A_1") (pintype "passive"))
      (node (ref "L2") (pin "2") (pinfunction "2_2") (pintype "passive"))
      (node (ref "P5") (pin "1") (pinfunction "1_1") (pintype "passive"))
      (node (ref "R13") (pin "2") (pinfunction "2_2") (pintype "passive"))
      (node (ref "R20") (pin "1") (pinfunction "1_1") (pintype "passive"))
      (node (ref "U1") (pin "10") (pintype "passive"))
      (node (ref "U1") (pin "2") (pintype "passive"))
      (node (ref "U1") (pin "4") (pintype "passive"))
      (node (ref "U1") (pin "6") (pintype "passive"))
      (node (ref "U1") (pin "8") (pintype "passive"))
      (node (ref "U4") (pin "1") (pinfunction "IN_1") (pintype "passive"))
    )
    (net (code "203") (name "12V") (class "Default")
      (node (ref "C15") (pin "1") (pinfunction "1_1") (pintype "passive"))
      (node (ref "C16") (pin "2") (pinfunction "2_2") (pintype "passive"))
      (node (ref "P2") (pin "1") (pinfunction "1_1") (pintype "passive"))
      (node (ref "U3") (pin "7") (pinfunction "IN_7") (pintype "passive"))
    )
    (net (code "204") (name "FEC_A3V2") (class "Default")
      (node (ref "C2") (pin "1") (pintype "passive"))
      (node (ref "C3") (pin "1") (pintype "passive"))
      (node (ref "L1") (pin "1") (pinfunction "1_1") (pintype "passive"))
      (node (ref "U2") (pin "1") (pinfunction "VDD2A_1") (pintype "passive"))
      (node (ref "U2") (pin "19") (pinfunction "VDD1A_19") (pintype "passive"))
    )
    (net (code "205") (name "GEN_3V3") (class "Default")
      (node (ref "C10") (pin "1") (pinfunction "1_1") (pintype "passive"))
      (node (ref "C14") (pin "2") (pinfunction "2_2") (pintype "passive"))
      (node (ref "C19") (pin "2") (pinfunction "2_2") (pintype "passive"))
      (node (ref "C4") (pin "2") (pintype "passive"))
      (node (ref "C8") (pin "2") (pintype "passive"))
      (node (ref "D5") (pin "1") (pinfunction "A_1") (pintype "passive"))
      (node (ref "L1") (pin "2") (pinfunction "2_2") (pintype "passive"))
      (node (ref "P1") (pin "9") (pinfunction "LED_G+_9") (pintype "passive"))
      (node (ref "P6") (pin "4") (pinfunction "4_4") (pintype "passive"))
      (node (ref "R1") (pin "2") (pinfunction "2_2") (pintype "passive"))
      (node (ref "R10") (pin "2") (pinfunction "2_2") (pintype "passive"))
      (node (ref "R11") (pin "2") (pinfunction "2_2") (pintype "passive"))
      (node (ref "R2") (pin "2") (pinfunction "2_2") (pintype "passive"))
      (node (ref "R21") (pin "2") (pinfunction "2_2") (pintype "passive"))
      (node (ref "R22") (pin "2") (pinfunction "2_2") (pintype "passive"))
      (node (ref "R24") (pin "1") (pinfunction "1_1") (pintype "passive"))
      (node (ref "R3") (pin "2") (pinfunction "2_2") (pintype "passive"))
      (node (ref "R4") (pin "2") (pinfunction "2_2") (pintype "passive"))
      (node (ref "R5") (pin "2") (pinfunction "2_2") (pintype "passive"))
      (node (ref "U2") (pin "9") (pinfunction "VDDIO_9") (pintype "passive"))
      (node (ref "U4") (pin "2") (pinfunction "OUT_2") (pintype "passive"))
      (node (ref "U5") (pin "18") (pinfunction "AVCC_18") (pintype "power_in"))
      (node (ref "U5") (pin "4") (pinfunction "VCC_4") (pintype "power_in"))
      (node (ref "U5") (pin "6") (pinfunction "VCC_6") (pintype "power_in"))
    )
    (net (code "206") (name "GND") (class "Default")
      (node (ref "C1") (pin "2") (pintype "passive"))
      (node (ref "C10") (pin "2") (pinfunction "2_2") (pintype "passive"))
      (node (ref "C11") (pin "2") (pinfunction "2_2") (pintype "passive"))
      (node (ref "C12") (pin "1") (pinfunction "1_1") (pintype "passive"))
      (node (ref "C14") (pin "1") (pinfunction "1_1") (pintype "passive"))
      (node (ref "C15") (pin "2") (pinfunction "2_2") (pintype "passive"))
      (node (ref "C16") (pin "1") (pinfunction "1_1") (pintype "passive"))
      (node (ref "C18") (pin "2") (pintype "passive"))
      (node (ref "C19") (pin "1") (pinfunction "1_1") (pintype "passive"))
      (node (ref "C2") (pin "2") (pintype "passive"))
      (node (ref "C22") (pin "2") (pinfunction "2_2") (pintype "passive"))
      (node (ref "C23") (pin "2") (pinfunction "2_2") (pintype "passive"))
      (node (ref "C3") (pin "2") (pintype "passive"))
      (node (ref "C4") (pin "1") (pintype "passive"))
      (node (ref "C5") (pin "2") (pintype "passive"))
      (node (ref "C6") (pin "2") (pintype "passive"))
      (node (ref "C7") (pin "1") (pinfunction "1_1") (pintype "passive"))
      (node (ref "C8") (pin "1") (pintype "passive"))
      (node (ref "D2") (pin "1") (pinfunction "A_1") (pintype "passive"))
      (node (ref "K1") (pin "1") (pintype "passive"))
      (node (ref "K1") (pin "2") (pintype "passive"))
      (node (ref "P1") (pin "11") (pinfunction "LED_Y-_11") (pintype "passive"))
      (node (ref "P1") (pin "13") (pinfunction "GND_13") (pintype "passive"))
      (node (ref "P1") (pin "14") (pinfunction "GND_14") (pintype "passive"))
      (node (ref "P1") (pin "8") (pinfunction "GND_8") (pintype "passive"))
      (node (ref "P2") (pin "2") (pinfunction "2_2") (pintype "passive"))
      (node (ref "P3") (pin "3") (pinfunction "3_3") (pintype "passive"))
      (node (ref "P4") (pin "15") (pinfunction "15_15") (pintype "passive"))
      (node (ref "P4") (pin "24") (pinfunction "24_24") (pintype "passive"))
      (node (ref "P4") (pin "33") (pinfunction "33_33") (pintype "passive"))
      (node (ref "P4") (pin "44") (pinfunction "44_44") (pintype "passive"))
      (node (ref "P4") (pin "50") (pinfunction "50_50") (pintype "passive"))
      (node (ref "P4") (pin "51") (pinfunction "51_51") (pintype "passive"))
      (node (ref "P4") (pin "6") (pinfunction "6_6") (pintype "passive"))
      (node (ref "P5") (pin "2") (pinfunction "2_2") (pintype "passive"))
      (node (ref "P6") (pin "1") (pinfunction "1_1") (pintype "passive"))
      (node (ref "P7") (pin "1") (pinfunction "1_1") (pintype "passive"))
      (node (ref "R12") (pin "2") (pinfunction "2_2") (pintype "passive"))
      (node (ref "R14") (pin "2") (pinfunction "2_2") (pintype "passive"))
      (node (ref "R15") (pin "1") (pinfunction "1_1") (pintype "passive"))
      (node (ref "R16") (pin "1") (pinfunction "1_1") (pintype "passive"))
      (node (ref "R17") (pin "1") (pinfunction "1_1") (pintype "passive"))
      (node (ref "R8") (pin "1") (pinfunction "1_1") (pintype "passive"))
      (node (ref "R9") (pin "1") (pinfunction "1_1") (pintype "passive"))
      (node (ref "U1") (pin "1") (pintype "passive"))
      (node (ref "U1") (pin "128") (pintype "passive"))
      (node (ref "U1") (pin "149") (pintype "passive"))
      (node (ref "U1") (pin "176") (pintype "passive"))
      (node (ref "U1") (pin "201") (pintype "passive"))
      (node (ref "U1") (pin "202") (pintype "passive"))
      (node (ref "U1") (pin "3") (pintype "passive"))
      (node (ref "U1") (pin "5") (pintype "passive"))
      (node (ref "U1") (pin "51") (pintype "passive"))
      (node (ref "U1") (pin "65") (pintype "passive"))
      (node (ref "U1") (pin "7") (pintype "passive"))
      (node (ref "U1") (pin "9") (pintype "passive"))
      (node (ref "U1") (pin "93") (pintype "passive"))
      (node (ref "U2") (pin "25") (pinfunction "VSS_25") (pintype "passive"))
      (node (ref "U3") (pin "6") (pinfunction "GND_6") (pintype "passive"))
      (node (ref "U3") (pin "9") (pinfunction "GND_9") (pintype "passive"))
      (node (ref "U4") (pin "3") (pinfunction "GND_3") (pintype "passive"))
      (node (ref "U4") (pin "6") (pinfunction "GND_6") (pintype "passive"))
      (node (ref "U5") (pin "21") (pinfunction "GND_21") (pintype "power_in"))
      (node (ref "U5") (pin "3") (pinfunction "GND_3") (pintype "power_in"))
      (node (ref "U5") (pin "5") (pinfunction "GND_5") (pintype "power_in"))
    )
    (net (code "207") (name "Net-(D2-K)") (class "Default")
      (node (ref "C20") (pin "1") (pinfunction "1_1") (pintype "passive"))
      (node (ref "D2") (pin "2") (pinfunction "K_2") (pintype "passive"))
      (node (ref "L2") (pin "1") (pinfunction "1_1") (pintype "passive"))
      (node (ref "U3") (pin "8") (pinfunction "SW_8") (pintype "passive"))
    )
    (net (code "208") (name "Net-(D3-K)") (class "Default")
      (node (ref "D3") (pin "2") (pinfunction "K_2") (pintype "passive"))
      (node (ref "R15") (pin "2") (pinfunction "2_2") (pintype "passive"))
    )
    (net (code "209") (name "Net-(D4-K)") (class "Default")
      (node (ref "D4") (pin "2") (pinfunction "K_2") (pintype "passive"))
      (node (ref "R16") (pin "2") (pinfunction "2_2") (pintype "passive"))
    )
    (net (code "210") (name "Net-(D5-K)") (class "Default")
      (node (ref "D5") (pin "2") (pinfunction "K_2") (pintype "passive"))
      (node (ref "R23") (pin "2") (pinfunction "2_2") (pintype "passive"))
    )
    (net (code "211") (name "Net-(P1-LED_G-)") (class "Default")
      (node (ref "P1") (pin "10") (pinfunction "LED_G-_10") (pintype "passive"))
      (node (ref "R7") (pin "1") (pinfunction "1_1") (pintype "passive"))
    )
    (net (code "212") (name "Net-(P1-LED_Y+)") (class "Default")
      (node (ref "P1") (pin "12") (pinfunction "LED_Y+_12") (pintype "passive"))
      (node (ref "R6") (pin "1") (pinfunction "1_1") (pintype "passive"))
    )
    (net (code "213") (name "Net-(P1-MRD)") (class "Default")
      (node (ref "C1") (pin "1") (pintype "passive"))
      (node (ref "P1") (pin "4") (pinfunction "MTD_4") (pintype "passive"))
      (node (ref "P1") (pin "5") (pinfunction "MRD_5") (pintype "passive"))
      (node (ref "R1") (pin "1") (pinfunction "1_1") (pintype "passive"))
    )
    (net (code "214") (name "Net-(P4-Pad46)") (class "Default")
      (node (ref "P4") (pin "46") (pinfunction "46_46") (pintype "passive"))
      (node (ref "R18") (pin "1") (pinfunction "1_1") (pintype "passive"))
    )
    (net (code "215") (name "Net-(R13-Pad1)") (class "Default")
      (node (ref "R13") (pin "1") (pinfunction "1_1") (pintype "passive"))
      (node (ref "R14") (pin "1") (pinfunction "1_1") (pintype "passive"))
      (node (ref "U3") (pin "4") (pinfunction "SW_4") (pintype "passive"))
    )
    (net (code "216") (name "Net-(U2-RBIAS)") (class "Default")
      (node (ref "R9") (pin "2") (pinfunction "2_2") (pintype "passive"))
      (node (ref "U2") (pin "24") (pinfunction "RBIAS_24") (pintype "passive"))
    )
    (net (code "217") (name "Net-(U2-VDDCR)") (class "Default")
      (node (ref "C5") (pin "1") (pintype "passive"))
      (node (ref "C6") (pin "1") (pintype "passive"))
      (node (ref "U2") (pin "6") (pinfunction "VDDCR_6") (pintype "passive"))
    )
    (net (code "218") (name "Net-(U2-XTAL1{slash}CLKIN)") (class "Default")
      (node (ref "R19") (pin "1") (pinfunction "1_1") (pintype "passive"))
      (node (ref "U2") (pin "5") (pinfunction "XTAL1/CLKIN_5") (pintype "passive"))
    )
    (net (code "219") (name "Net-(U3-BOOT)") (class "Default")
      (node (ref "C20") (pin "2") (pinfunction "2_2") (pintype "passive"))
      (node (ref "U3") (pin "1") (pinfunction "BOOT_1") (pintype "passive"))
    )
    (net (code "220") (name "Net-(U4-NR{slash}FB)") (class "Default")
      (node (ref "R11") (pin "1") (pinfunction "1_1") (pintype "passive"))
      (node (ref "R12") (pin "1") (pinfunction "1_1") (pintype "passive"))
      (node (ref "U4") (pin "4") (pinfunction "NR/FB_4") (pintype "passive"))
    )
    (net (code "221") (name "Net-(U5-AREF)") (class "Default")
      (node (ref "C23") (pin "1") (pinfunction "1_1") (pintype "passive"))
      (node (ref "U5") (pin "20") (pinfunction "AREF_20") (pintype "passive"))
    )
    (net (code "222") (name "Net-(U5-PD4_(XCK{slash}T0))") (class "Default")
      (node (ref "R23") (pin "1") (pinfunction "1_1") (pintype "passive"))
      (node (ref "U5") (pin "2") (pinfunction "PD4_(XCK/T0)_2") (pintype "bidirectional"))
    )
    (net (code "223") (name "unconnected-(P1-NC-Pad7)") (class "Default")
      (node (ref "P1") (pin "7") (pinfunction "NC_7") (pintype "passive+no_connect"))
    )
    (net (code "224") (name "unconnected-(P4-Pad34)") (class "Default")
      (node (ref "P4") (pin "34") (pinfunction "34_34") (pintype "passive"))
    )
    (net (code "225") (name "unconnected-(P4-Pad35)") (class "Default")
      (node (ref "P4") (pin "35") (pinfunction "35_35") (pintype "passive"))
    )
    (net (code "226") (name "unconnected-(P4-Pad36)") (class "Default")
      (node (ref "P4") (pin "36") (pinfunction "36_36") (pintype "passive"))
    )
    (net (code "227") (name "unconnected-(P4-Pad39)") (class "Default")
      (node (ref "P4") (pin "39") (pinfunction "39_39") (pintype "passive"))
    )
    (net (code "228") (name "unconnected-(P4-Pad40)") (class "Default")
      (node (ref "P4") (pin "40") (pinfunction "40_40") (pintype "passive"))
    )
    (net (code "229") (name "unconnected-(P4-Pad47)") (class "Default")
      (node (ref "P4") (pin "47") (pinfunction "47_47") (pintype "passive"))
    )
    (net (code "230") (name "unconnected-(P4-Pad48)") (class "Default")
      (node (ref "P4") (pin "48") (pinfunction "48_48") (pintype "passive"))
    )
    (net (code "231") (name "unconnected-(P4-Pad49)") (class "Default")
      (node (ref "P4") (pin "49") (pinfunction "49_49") (pintype "passive"))
    )
    (net (code "232") (name "unconnected-(U2-XTAL2-Pad4)") (class "Default")
      (node (ref "U2") (pin "4") (pinfunction "XTAL2_4") (pintype "passive+no_connect"))
    )
    (net (code "233") (name "unconnected-(U3-EN-Pad5)") (class "Default")
      (node (ref "U3") (pin "5") (pinfunction "EN_5") (pintype "passive"))
    )
    (net (code "234") (name "unconnected-(U5-ADC6-Pad19)") (class "Default")
      (node (ref "U5") (pin "19") (pinfunction "ADC6_19") (pintype "input"))
    )
    (net (code "235") (name "unconnected-(U5-ADC7-Pad22)") (class "Default")
      (node (ref "U5") (pin "22") (pinfunction "ADC7_22") (pintype "input"))
    )
    (net (code "236") (name "unconnected-(U5-PB2_(~{SS}{slash}OC1B)-Pad14)") (class "Default")
      (node (ref "U5") (pin "14") (pinfunction "PB2_(~{SS}/OC1B)_14") (pintype "bidirectional"))
    )
    (net (code "237") (name "unconnected-(U5-PB6_(XTAL1{slash}TOSC1)-Pad7)") (class "Default")
      (node (ref "U5") (pin "7") (pinfunction "PB6_(XTAL1/TOSC1)_7") (pintype "bidirectional"))
    )
    (net (code "238") (name "unconnected-(U5-PB7_(XTAL2{slash}TOSC2)-Pad8)") (class "Default")
      (node (ref "U5") (pin "8") (pinfunction "PB7_(XTAL2/TOSC2)_8") (pintype "bidirectional"))
    )
    (net (code "239") (name "unconnected-(U5-PC0_(ADC0)-Pad23)") (class "Default")
      (node (ref "U5") (pin "23") (pinfunction "PC0_(ADC0)_23") (pintype "bidirectional"))
    )
    (net (code "240") (name "unconnected-(U5-PC1_(ADC1)-Pad24)") (class "Default")
      (node (ref "U5") (pin "24") (pinfunction "PC1_(ADC1)_24") (pintype "bidirectional"))
    )
    (net (code "241") (name "unconnected-(U5-PC2_(ADC2)-Pad25)") (class "Default")
      (node (ref "U5") (pin "25") (pinfunction "PC2_(ADC2)_25") (pintype "bidirectional"))
    )
    (net (code "242") (name "unconnected-(U5-PC3_(ADC3)-Pad26)") (class "Default")
      (node (ref "U5") (pin "26") (pinfunction "PC3_(ADC3)_26") (pintype "bidirectional"))
    )
    (net (code "243") (name "unconnected-(U5-PC4_(ADC4{slash}SDA)-Pad27)") (class "Default")
      (node (ref "U5") (pin "27") (pinfunction "PC4_(ADC4/SDA)_27") (pintype "bidirectional"))
    )
    (net (code "244") (name "unconnected-(U5-PC5_(ADC5{slash}SCL)-Pad28)") (class "Default")
      (node (ref "U5") (pin "28") (pinfunction "PC5_(ADC5/SCL)_28") (pintype "bidirectional"))
    )
    (net (code "245") (name "unconnected-(U5-PD3_(INT1)-Pad1)") (class "Default")
      (node (ref "U5") (pin "1") (pinfunction "PD3_(INT1)_1") (pintype "bidirectional"))
    )
    (net (code "246") (name "unconnected-(U5-PD5_(T1)-Pad9)") (class "Default")
      (node (ref "U5") (pin "9") (pinfunction "PD5_(T1)_9") (pintype "bidirectional"))
    )
    (net (code "247") (name "unconnected-(U5-PD6_(AIN0)-Pad10)") (class "Default")
      (node (ref "U5") (pin "10") (pinfunction "PD6_(AIN0)_10") (pintype "bidirectional"))
    )
    (net (code "248") (name "unconnected-(U5-PD7_(AIN1)-Pad11)") (class "Default")
      (node (ref "U5") (pin "11") (pinfunction "PD7_(AIN1)_11") (pintype "bidirectional"))
    )
  )
)
